# SAMV71_Xplained_Ultra_Power_Multiplexer.net
KiCad netlist of a schematic drawn in Altium Designer
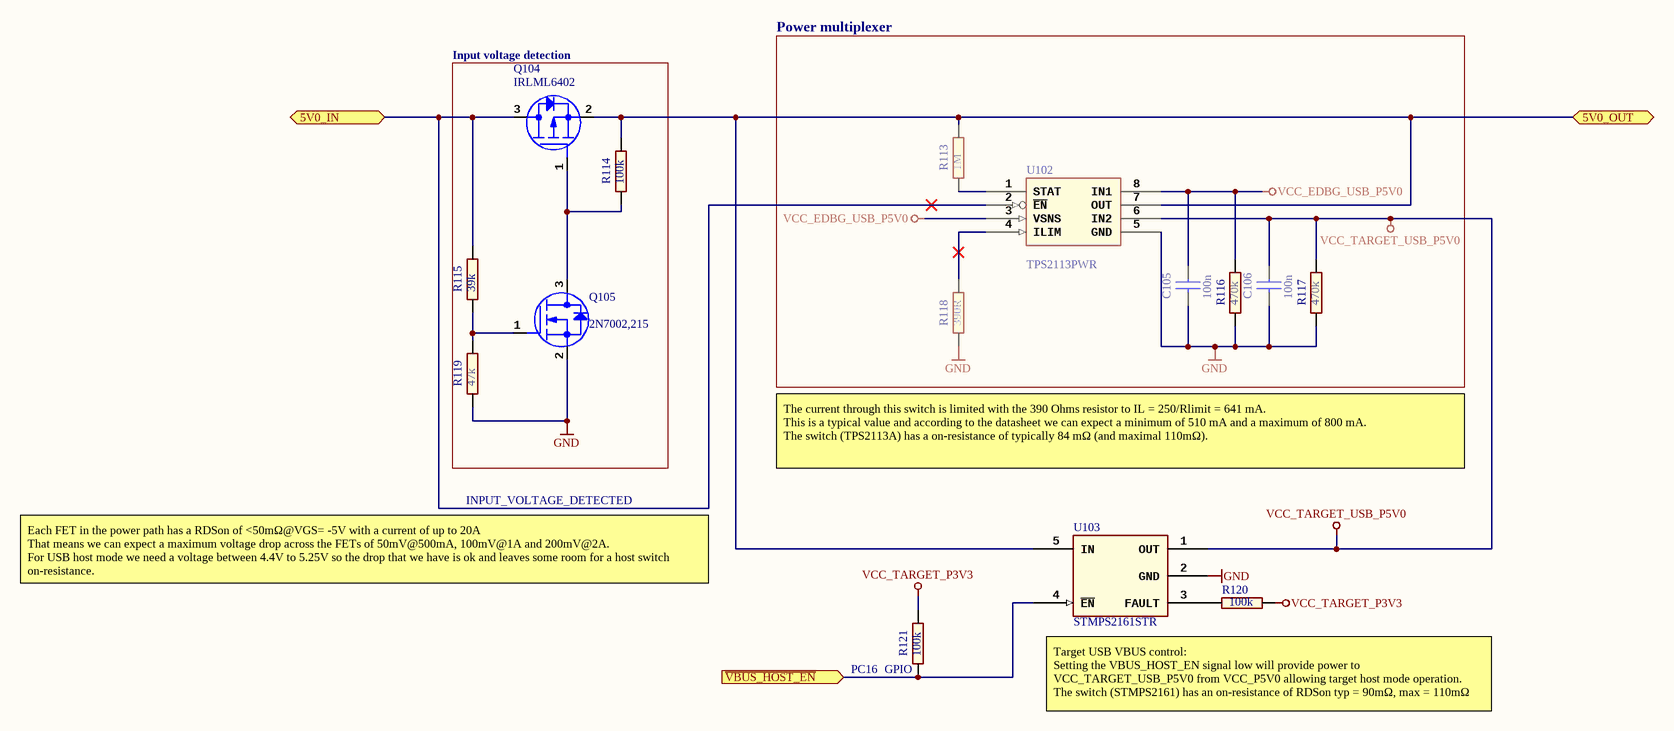
[diagram p0: SAMV71_Xplained_Ultra_Power_Multiplexer.SchDoc]

(export (version "E")
  (design (tool "Eeschema 10.0.6"))
  (components
    (comp (ref "C105")
      (value "100n")
      (footprint "AP1-00001")
      (description "Ceramic capacitor, SMD 0402, X7R, 16V, +/-10%")
      (fields (field (name "TOLERANCE") "16V, +/-10%") (field (name "MANUFACTURER") "Kemet"))
      (libsource (lib "AltiumDbLib") (part "CAP-NONPOL"))
    )
    (comp (ref "C106")
      (value "100n")
      (footprint "AP1-00001")
      (description "Ceramic capacitor, SMD 0402, X7R, 16V, +/-10%")
      (fields (field (name "TOLERANCE") "16V, +/-10%") (field (name "MANUFACTURER") "Kemet"))
      (libsource (lib "AltiumDbLib") (part "CAP-NONPOL"))
    )
    (comp (ref "Q104")
      (value "IRLML6402")
      (footprint "AP5-00002")
      (description "P-ch. MOSFET. -30V, -3.7A continuous,RDS(ON)=0.05Ohm@VGS=-4,5V, RDS(ON)=0.08Ohm@VGS=-2.5V")
      (fields (field (name "MANUFACTURER") "International Rectifier") (field (name "MPN") "IRLML6402PBF"))
      (libsource (lib "AltiumDbLib") (part "MOSFET_P_GSD"))
    )
    (comp (ref "Q105")
      (value "2N7002,215")
      (footprint "AP5-00002")
      (description "N-Channel MOSFET. 60V, 0.300A continuous, 1.2A Peak. RDS(ON) = 3.8Ohm@VGS=4.5V, VGS(th)<2.5V")
      (fields (field (name "MANUFACTURER") "NXP"))
      (libsource (lib "AltiumDbLib") (part "MOSFET_N_GSD"))
    )
    (comp (ref "R113")
      (value "1M")
      (footprint "AP2-00000")
      (description "Thick film resistor, SMD 0402, 1/16W, 1%")
      (fields (field (name "TOLERANCE") "1 %"))
      (libsource (lib "AltiumDbLib") (part "R2"))
    )
    (comp (ref "R114")
      (value "100k")
      (footprint "AP2-00000")
      (description "Thick film resistor, SMD 0402, 1/16W, 1%")
      (fields (field (name "TOLERANCE") "1 %"))
      (libsource (lib "AltiumDbLib") (part "R2"))
    )
    (comp (ref "R115")
      (value "39k")
      (footprint "AP2-00000")
      (description "Thick film resistor, SMD 0402, 1/16W, 1%")
      (fields (field (name "TOLERANCE") "1 %"))
      (libsource (lib "AltiumDbLib") (part "R2"))
    )
    (comp (ref "R116")
      (value "470k")
      (footprint "AP2-00000")
      (description "Thick film resistor, SMD 0402, 1/16W, 1%")
      (fields (field (name "TOLERANCE") "1 %"))
      (libsource (lib "AltiumDbLib") (part "R2"))
    )
    (comp (ref "R117")
      (value "470k")
      (footprint "AP2-00000")
      (description "Thick film resistor, SMD 0402, 1/16W, 1%")
      (fields (field (name "TOLERANCE") "1 %"))
      (libsource (lib "AltiumDbLib") (part "R2"))
    )
    (comp (ref "R118")
      (value "390R")
      (footprint "AP2-00000")
      (description "Thick film resistor, SMD 0402, 1/16W, 1%")
      (fields (field (name "TOLERANCE") "1 %"))
      (libsource (lib "AltiumDbLib") (part "R2"))
    )
    (comp (ref "R119")
      (value "47k")
      (footprint "AP2-00000")
      (description "Thick film resistor, SMD 0402, 1/16W, 1%")
      (fields (field (name "TOLERANCE") "1 %"))
      (libsource (lib "AltiumDbLib") (part "R2"))
    )
    (comp (ref "R120")
      (value "100k")
      (footprint "AP2-00011")
      (description "Thick film resistor, SMD 0402, 1/16W, 1%")
      (fields (field (name "TOLERANCE") "1 %"))
      (libsource (lib "") (part "R2_1"))
    )
    (comp (ref "R121")
      (value "100k")
      (footprint "AP2-00011")
      (description "Thick film resistor, SMD 0402, 1/16W, 1%")
      (fields (field (name "TOLERANCE") "1 %"))
      (libsource (lib "AltiumDbLib") (part "R2"))
    )
    (comp (ref "U102")
      (value "TPS2113PWR")
      (footprint "AP6-00054")
      (description "Autoswitching 2:1 Power Mux")
      (fields (field (name "MANUFACTURER") "Texas Instruments"))
      (libsource (lib "AltiumDbLib") (part "TPS2112"))
    )
    (comp (ref "U103")
      (value "STMPS2161STR")
      (footprint "AP6-00087")
      (description "Single channel power switch, 1A, reverse block, active low enabled.")
      (fields (field (name "TOLERANCE") "2.7 to 5.5V") (field (name "MANUFACTURER") "ST"))
      (libsource (lib "AltiumDbLib") (part "STMPS2161"))
    )
  )
  (nets
    (net (code "1") (name "/5V0_IN") (class "Default")
      (node (ref "Q104") (pin "3") (pinfunction "D_3") (pintype "passive"))
      (node (ref "R115") (pin "2") (pinfunction "2_2") (pintype "passive"))
      (node (ref "U102") (pin "2") (pinfunction "~{EN}_2") (pintype "input"))
    )
    (net (code "2") (name "/5V0_OUT") (class "Default")
      (node (ref "Q104") (pin "2") (pinfunction "S_2") (pintype "passive"))
      (node (ref "R113") (pin "2") (pinfunction "2_2") (pintype "passive"))
      (node (ref "R114") (pin "2") (pinfunction "2_2") (pintype "passive"))
      (node (ref "U102") (pin "7") (pinfunction "OUT_7") (pintype "power_in"))
      (node (ref "U103") (pin "5") (pinfunction "IN_5") (pintype "power_in"))
    )
    (net (code "3") (name "/~{VBUS_HOST_EN}") (class "Default")
      (node (ref "R121") (pin "1") (pinfunction "1_1") (pintype "passive"))
      (node (ref "U103") (pin "4") (pinfunction "~{EN}_4") (pintype "input"))
    )
    (net (code "4") (name "GND") (class "Default")
      (node (ref "C105") (pin "2") (pinfunction "2_2") (pintype "passive"))
      (node (ref "C106") (pin "2") (pinfunction "2_2") (pintype "passive"))
      (node (ref "Q105") (pin "2") (pinfunction "S_2") (pintype "passive"))
      (node (ref "R116") (pin "1") (pinfunction "1_1") (pintype "passive"))
      (node (ref "R117") (pin "1") (pinfunction "1_1") (pintype "passive"))
      (node (ref "R118") (pin "1") (pinfunction "1_1") (pintype "passive"))
      (node (ref "R119") (pin "1") (pinfunction "1_1") (pintype "passive"))
      (node (ref "U102") (pin "5") (pinfunction "GND_5") (pintype "power_in"))
      (node (ref "U103") (pin "2") (pinfunction "GND_2") (pintype "power_in"))
    )
    (net (code "5") (name "Net-(Q104-G)") (class "Default")
      (node (ref "Q104") (pin "1") (pinfunction "G_1") (pintype "passive"))
      (node (ref "Q105") (pin "3") (pinfunction "D_3") (pintype "passive"))
      (node (ref "R114") (pin "1") (pinfunction "1_1") (pintype "passive"))
    )
    (net (code "6") (name "Net-(Q105-G)") (class "Default")
      (node (ref "Q105") (pin "1") (pinfunction "G_1") (pintype "passive"))
      (node (ref "R115") (pin "1") (pinfunction "1_1") (pintype "passive"))
      (node (ref "R119") (pin "2") (pinfunction "2_2") (pintype "passive"))
    )
    (net (code "7") (name "Net-(U102-ILIM)") (class "Default")
      (node (ref "R118") (pin "2") (pinfunction "2_2") (pintype "passive"))
      (node (ref "U102") (pin "4") (pinfunction "ILIM_4") (pintype "input"))
    )
    (net (code "8") (name "Net-(U102-STAT)") (class "Default")
      (node (ref "R113") (pin "1") (pinfunction "1_1") (pintype "passive"))
      (node (ref "U102") (pin "1") (pinfunction "STAT_1") (pintype "open_collector"))
    )
    (net (code "9") (name "Net-(U103-FAULT)") (class "Default")
      (node (ref "R120") (pin "2") (pinfunction "2_2") (pintype "passive"))
      (node (ref "U103") (pin "3") (pinfunction "FAULT_3") (pintype "open_collector"))
    )
    (net (code "10") (name "VCC_EDBG_USB_P5V0") (class "Default")
      (node (ref "C105") (pin "1") (pinfunction "1_1") (pintype "passive"))
      (node (ref "R116") (pin "2") (pinfunction "2_2") (pintype "passive"))
      (node (ref "U102") (pin "3") (pinfunction "VSNS_3") (pintype "input"))
      (node (ref "U102") (pin "8") (pinfunction "IN1_8") (pintype "power_in"))
    )
    (net (code "11") (name "VCC_TARGET_P3V3") (class "Default")
      (node (ref "R120") (pin "1") (pinfunction "1_1") (pintype "passive"))
      (node (ref "R121") (pin "2") (pinfunction "2_2") (pintype "passive"))
    )
    (net (code "12") (name "VCC_TARGET_USB_P5V0") (class "Default")
      (node (ref "C106") (pin "1") (pinfunction "1_1") (pintype "passive"))
      (node (ref "R117") (pin "2") (pinfunction "2_2") (pintype "passive"))
      (node (ref "U102") (pin "6") (pinfunction "IN2_6") (pintype "power_in"))
      (node (ref "U103") (pin "1") (pinfunction "OUT_1") (pintype "power_in"))
    )
  )
)
